# Safety_2019_V_3_0_uController.net
KiCad netlist of a schematic drawn in Altium Designer
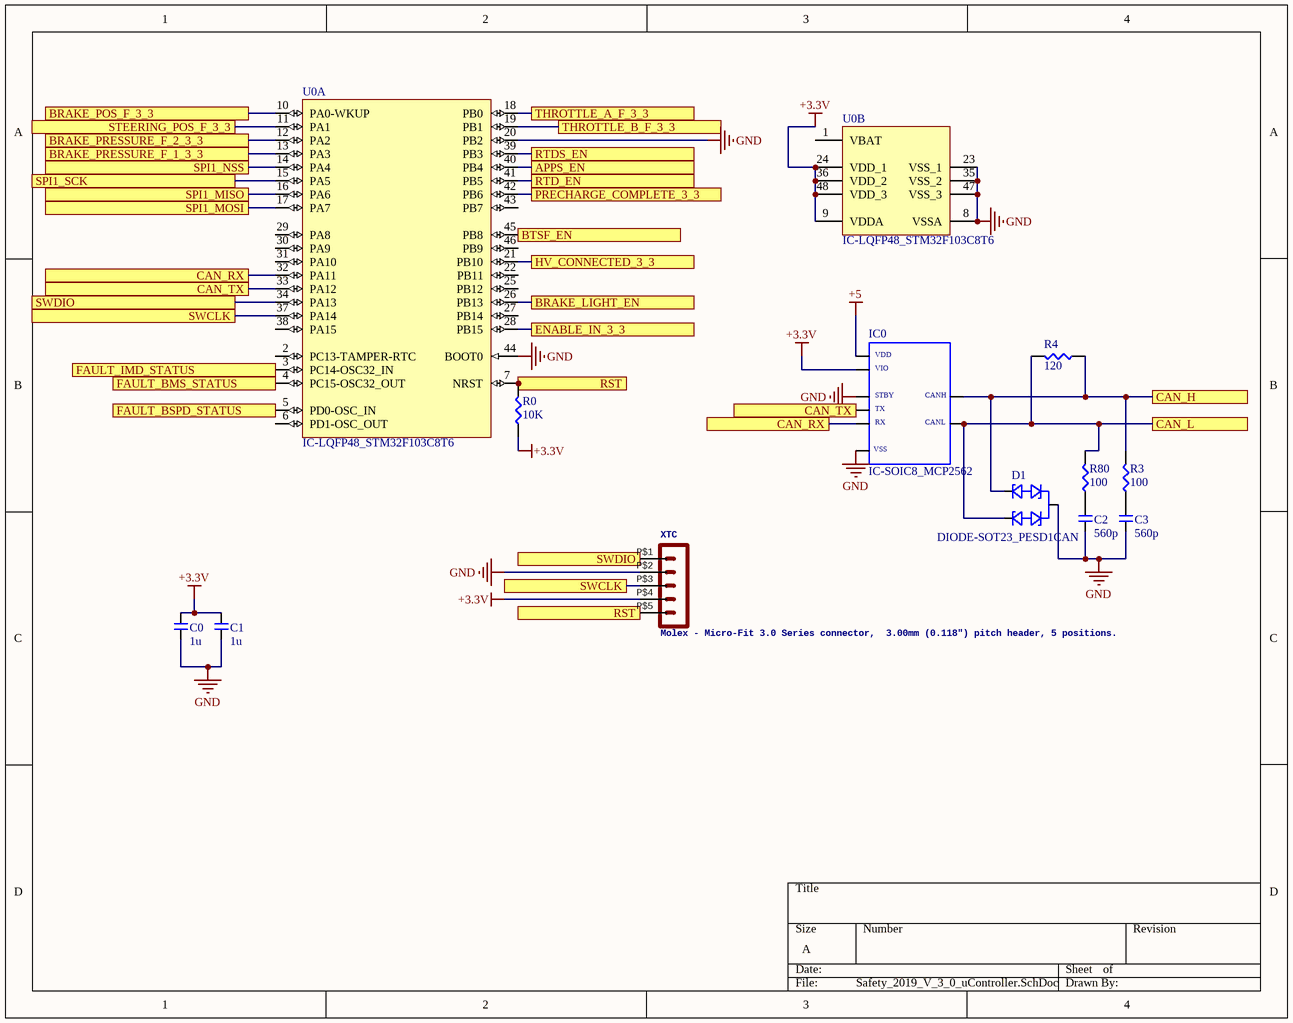
[diagram p0: Safety_2019_V_3_0_uController.SchDoc]

(export (version "E")
  (design (tool "Eeschema 10.0.6"))
  (components
    (comp (ref "C0")
      (value "1u")
      (footprint "CAP-0603")
      (libsource (lib "ife19_Elec_Library") (part "CAP-0603"))
    )
    (comp (ref "C1")
      (value "1u")
      (footprint "CAP-0603")
      (libsource (lib "ife19_Elec_Library") (part "CAP-0603"))
    )
    (comp (ref "C2")
      (value "560p")
      (footprint "CAP-0603")
      (libsource (lib "ife19_Elec_Library") (part "CAP-0603"))
    )
    (comp (ref "C3")
      (value "560p")
      (footprint "CAP-0603")
      (libsource (lib "ife19_Elec_Library") (part "CAP-0603"))
    )
    (comp (ref "D1")
      (value "DIODE-SOT23_PESD1CAN")
      (footprint "SOT23")
      (libsource (lib "ife19_Elec_Library") (part "DIODE-SOT23_PESD1CAN"))
    )
    (comp (ref "IC0")
      (value "IC-SOIC8_MCP2562")
      (footprint "SOIC8")
      (libsource (lib "ife19_Elec_Library") (part "IC-SOIC8_MCP2562"))
    )
    (comp (ref "R0")
      (value "10K")
      (footprint "RES-0603")
      (libsource (lib "ife19_Elec_Library") (part "RES-0603"))
    )
    (comp (ref "R3")
      (value "100")
      (footprint "RES-0603")
      (libsource (lib "ife19_Elec_Library") (part "RES-0603"))
    )
    (comp (ref "R4")
      (value "120")
      (footprint "RES-0603")
      (libsource (lib "ife19_Elec_Library") (part "RES-0603"))
    )
    (comp (ref "R80")
      (value "100")
      (footprint "RES-0603")
      (libsource (lib "ife19_Elec_Library") (part "RES-0603"))
    )
    (comp (ref "U0")
      (value "IC-LQFP48_STM32F103C8T6")
      (footprint "STM-LQFP48_M")
      (fields (field (name "PARTNUMBER") "STM32F103C8T6"))
      (libsource (lib "ife19_Elec_Library") (part "IC-LQFP48_STM32F103C8T6"))
    )
    (comp (ref "XTC")
      (value "Molex - Micro-Fit 3.0 Series connector,  3.00mm (0.118\") pitch header, 5 positions.")
      (footprint "POS5_254MM_MALE")
      (libsource (lib "ife19_Elec_Conn_Library") (part "POS5_254MM_MALE"))
    )
  )
  (nets
    (net (code "1") (name "+3.3V") (class "Default")
      (node (ref "C0") (pin "2") (pinfunction "2_2") (pintype "passive"))
      (node (ref "C1") (pin "2") (pinfunction "2_2") (pintype "passive"))
      (node (ref "IC0") (pin "5") (pinfunction "5_5") (pintype "passive"))
      (node (ref "R0") (pin "1") (pinfunction "1_1") (pintype "passive"))
      (node (ref "U0") (pin "24") (pinfunction "VDD_1_24") (pintype "power_in"))
      (node (ref "U0") (pin "36") (pinfunction "VDD_2_36") (pintype "power_in"))
      (node (ref "U0") (pin "48") (pinfunction "VDD_3_48") (pintype "power_in"))
      (node (ref "U0") (pin "9") (pinfunction "VDDA_9") (pintype "power_in"))
      (node (ref "XTC") (pin "P$4") (pinfunction "4_P$4") (pintype "passive"))
    )
    (net (code "2") (name "+5") (class "Default")
      (node (ref "IC0") (pin "3") (pinfunction "3_3") (pintype "passive"))
    )
    (net (code "3") (name "/APPS_EN") (class "Default")
      (node (ref "U0") (pin "40") (pinfunction "PB4_40") (pintype "bidirectional"))
    )
    (net (code "4") (name "/BRAKE_LIGHT_EN") (class "Default")
      (node (ref "U0") (pin "26") (pinfunction "PB13_26") (pintype "bidirectional"))
    )
    (net (code "5") (name "/BRAKE_POS_F_3_3") (class "Default")
      (node (ref "U0") (pin "10") (pinfunction "PA0-WKUP_10") (pintype "bidirectional"))
    )
    (net (code "6") (name "/BRAKE_PRESSURE_F_1_3_3") (class "Default")
      (node (ref "U0") (pin "13") (pinfunction "PA3_13") (pintype "bidirectional"))
    )
    (net (code "7") (name "/BRAKE_PRESSURE_F_2_3_3") (class "Default")
      (node (ref "U0") (pin "12") (pinfunction "PA2_12") (pintype "bidirectional"))
    )
    (net (code "8") (name "/BTSF_EN") (class "Default")
      (node (ref "U0") (pin "45") (pinfunction "PB8_45") (pintype "bidirectional"))
    )
    (net (code "9") (name "/CAN_H") (class "Default")
      (node (ref "D1") (pin "1") (pinfunction "CAN1_1") (pintype "passive"))
      (node (ref "IC0") (pin "7") (pinfunction "7_7") (pintype "passive"))
      (node (ref "R3") (pin "2") (pinfunction "2_2") (pintype "passive"))
      (node (ref "R4") (pin "1") (pinfunction "1_1") (pintype "passive"))
    )
    (net (code "10") (name "/CAN_L") (class "Default")
      (node (ref "D1") (pin "2") (pinfunction "CAN2_2") (pintype "passive"))
      (node (ref "IC0") (pin "6") (pinfunction "6_6") (pintype "passive"))
      (node (ref "R4") (pin "2") (pinfunction "2_2") (pintype "passive"))
      (node (ref "R80") (pin "2") (pinfunction "2_2") (pintype "passive"))
    )
    (net (code "11") (name "/CAN_RX") (class "Default")
      (node (ref "IC0") (pin "4") (pinfunction "4_4") (pintype "passive"))
      (node (ref "U0") (pin "32") (pinfunction "PA11_32") (pintype "bidirectional"))
    )
    (net (code "12") (name "/CAN_TX") (class "Default")
      (node (ref "IC0") (pin "1") (pinfunction "1_1") (pintype "passive"))
      (node (ref "U0") (pin "33") (pinfunction "PA12_33") (pintype "bidirectional"))
    )
    (net (code "13") (name "/ENABLE_IN_3_3") (class "Default")
      (node (ref "U0") (pin "28") (pinfunction "PB15_28") (pintype "bidirectional"))
    )
    (net (code "14") (name "/FAULT_BMS_STATUS") (class "Default")
      (node (ref "U0") (pin "4") (pinfunction "PC15-OSC32_OUT_4") (pintype "bidirectional"))
    )
    (net (code "15") (name "/FAULT_BSPD_STATUS") (class "Default")
      (node (ref "U0") (pin "5") (pinfunction "PD0-OSC_IN_5") (pintype "bidirectional"))
    )
    (net (code "16") (name "/FAULT_IMD_STATUS") (class "Default")
      (node (ref "U0") (pin "3") (pinfunction "PC14-OSC32_IN_3") (pintype "bidirectional"))
    )
    (net (code "17") (name "/HV_CONNECTED_3_3") (class "Default")
      (node (ref "U0") (pin "21") (pinfunction "PB10_21") (pintype "bidirectional"))
    )
    (net (code "18") (name "/PRECHARGE_COMPLETE_3_3") (class "Default")
      (node (ref "U0") (pin "42") (pinfunction "PB6_42") (pintype "bidirectional"))
    )
    (net (code "19") (name "/RST") (class "Default")
      (node (ref "R0") (pin "2") (pinfunction "2_2") (pintype "passive"))
      (node (ref "U0") (pin "7") (pinfunction "NRST_7") (pintype "bidirectional"))
      (node (ref "XTC") (pin "P$5") (pinfunction "5_P$5") (pintype "passive"))
    )
    (net (code "20") (name "/RTDS_EN") (class "Default")
      (node (ref "U0") (pin "39") (pinfunction "PB3_39") (pintype "bidirectional"))
    )
    (net (code "21") (name "/RTD_EN") (class "Default")
      (node (ref "U0") (pin "41") (pinfunction "PB5_41") (pintype "bidirectional"))
    )
    (net (code "22") (name "/SPI1_MISO") (class "Default")
      (node (ref "U0") (pin "16") (pinfunction "PA6_16") (pintype "bidirectional"))
    )
    (net (code "23") (name "/SPI1_MOSI") (class "Default")
      (node (ref "U0") (pin "17") (pinfunction "PA7_17") (pintype "bidirectional"))
    )
    (net (code "24") (name "/SPI1_NSS") (class "Default")
      (node (ref "U0") (pin "14") (pinfunction "PA4_14") (pintype "bidirectional"))
    )
    (net (code "25") (name "/SPI1_SCK") (class "Default")
      (node (ref "U0") (pin "15") (pinfunction "PA5_15") (pintype "bidirectional"))
    )
    (net (code "26") (name "/STEERING_POS_F_3_3") (class "Default")
      (node (ref "U0") (pin "11") (pinfunction "PA1_11") (pintype "bidirectional"))
    )
    (net (code "27") (name "/SWCLK") (class "Default")
      (node (ref "U0") (pin "37") (pinfunction "PA14_37") (pintype "bidirectional"))
      (node (ref "XTC") (pin "P$3") (pinfunction "3_P$3") (pintype "passive"))
    )
    (net (code "28") (name "/SWDIO") (class "Default")
      (node (ref "U0") (pin "34") (pinfunction "PA13_34") (pintype "bidirectional"))
      (node (ref "XTC") (pin "P$1") (pinfunction "1_P$1") (pintype "passive"))
    )
    (net (code "29") (name "/THROTTLE_A_F_3_3") (class "Default")
      (node (ref "U0") (pin "18") (pinfunction "PB0_18") (pintype "bidirectional"))
    )
    (net (code "30") (name "/THROTTLE_B_F_3_3") (class "Default")
      (node (ref "U0") (pin "19") (pinfunction "PB1_19") (pintype "bidirectional"))
    )
    (net (code "31") (name "GND") (class "Default")
      (node (ref "C0") (pin "1") (pinfunction "1_1") (pintype "passive"))
      (node (ref "C1") (pin "1") (pinfunction "1_1") (pintype "passive"))
      (node (ref "C2") (pin "1") (pinfunction "1_1") (pintype "passive"))
      (node (ref "C3") (pin "1") (pinfunction "1_1") (pintype "passive"))
      (node (ref "D1") (pin "3") (pinfunction "G_3") (pintype "passive"))
      (node (ref "IC0") (pin "2") (pinfunction "2_2") (pintype "passive"))
      (node (ref "IC0") (pin "8") (pinfunction "8_8") (pintype "passive"))
      (node (ref "U0") (pin "20") (pinfunction "PB2_20") (pintype "bidirectional"))
      (node (ref "U0") (pin "23") (pinfunction "VSS_1_23") (pintype "power_in"))
      (node (ref "U0") (pin "35") (pinfunction "VSS_2_35") (pintype "power_in"))
      (node (ref "U0") (pin "44") (pinfunction "BOOT0_44") (pintype "input"))
      (node (ref "U0") (pin "47") (pinfunction "VSS_3_47") (pintype "power_in"))
      (node (ref "U0") (pin "8") (pinfunction "VSSA_8") (pintype "power_in"))
      (node (ref "XTC") (pin "P$2") (pinfunction "2_P$2") (pintype "passive"))
    )
    (net (code "32") (name "Net-(C2-Pad2)") (class "Default")
      (node (ref "C2") (pin "2") (pinfunction "2_2") (pintype "passive"))
      (node (ref "R80") (pin "1") (pinfunction "1_1") (pintype "passive"))
    )
    (net (code "33") (name "Net-(C3-Pad2)") (class "Default")
      (node (ref "C3") (pin "2") (pinfunction "2_2") (pintype "passive"))
      (node (ref "R3") (pin "1") (pinfunction "1_1") (pintype "passive"))
    )
    (net (code "34") (name "unconnected-(U0A-PA8-Pad29)") (class "Default")
      (node (ref "U0") (pin "29") (pinfunction "PA8_29") (pintype "bidirectional"))
    )
    (net (code "35") (name "unconnected-(U0A-PA9-Pad30)") (class "Default")
      (node (ref "U0") (pin "30") (pinfunction "PA9_30") (pintype "bidirectional"))
    )
    (net (code "36") (name "unconnected-(U0A-PA10-Pad31)") (class "Default")
      (node (ref "U0") (pin "31") (pinfunction "PA10_31") (pintype "bidirectional"))
    )
    (net (code "37") (name "unconnected-(U0A-PA15-Pad38)") (class "Default")
      (node (ref "U0") (pin "38") (pinfunction "PA15_38") (pintype "bidirectional"))
    )
    (net (code "38") (name "unconnected-(U0A-PB7-Pad43)") (class "Default")
      (node (ref "U0") (pin "43") (pinfunction "PB7_43") (pintype "bidirectional"))
    )
    (net (code "39") (name "unconnected-(U0A-PB9-Pad46)") (class "Default")
      (node (ref "U0") (pin "46") (pinfunction "PB9_46") (pintype "bidirectional"))
    )
    (net (code "40") (name "unconnected-(U0A-PB11-Pad22)") (class "Default")
      (node (ref "U0") (pin "22") (pinfunction "PB11_22") (pintype "bidirectional"))
    )
    (net (code "41") (name "unconnected-(U0A-PB12-Pad25)") (class "Default")
      (node (ref "U0") (pin "25") (pinfunction "PB12_25") (pintype "bidirectional"))
    )
    (net (code "42") (name "unconnected-(U0A-PB14-Pad27)") (class "Default")
      (node (ref "U0") (pin "27") (pinfunction "PB14_27") (pintype "bidirectional"))
    )
    (net (code "43") (name "unconnected-(U0A-PC13-TAMPER-RTC-Pad2)") (class "Default")
      (node (ref "U0") (pin "2") (pinfunction "PC13-TAMPER-RTC_2") (pintype "bidirectional"))
    )
    (net (code "44") (name "unconnected-(U0A-PD1-OSC_OUT-Pad6)") (class "Default")
      (node (ref "U0") (pin "6") (pinfunction "PD1-OSC_OUT_6") (pintype "bidirectional"))
    )
    (net (code "45") (name "unconnected-(U0B-VBAT-Pad1)") (class "Default")
      (node (ref "U0") (pin "1") (pinfunction "VBAT_1") (pintype "power_in"))
    )
  )
)
